# openSX70_WIP_NEW_LAYOUT_20171230_V31_man.net
KiCad netlist of a schematic drawn in EAGLE
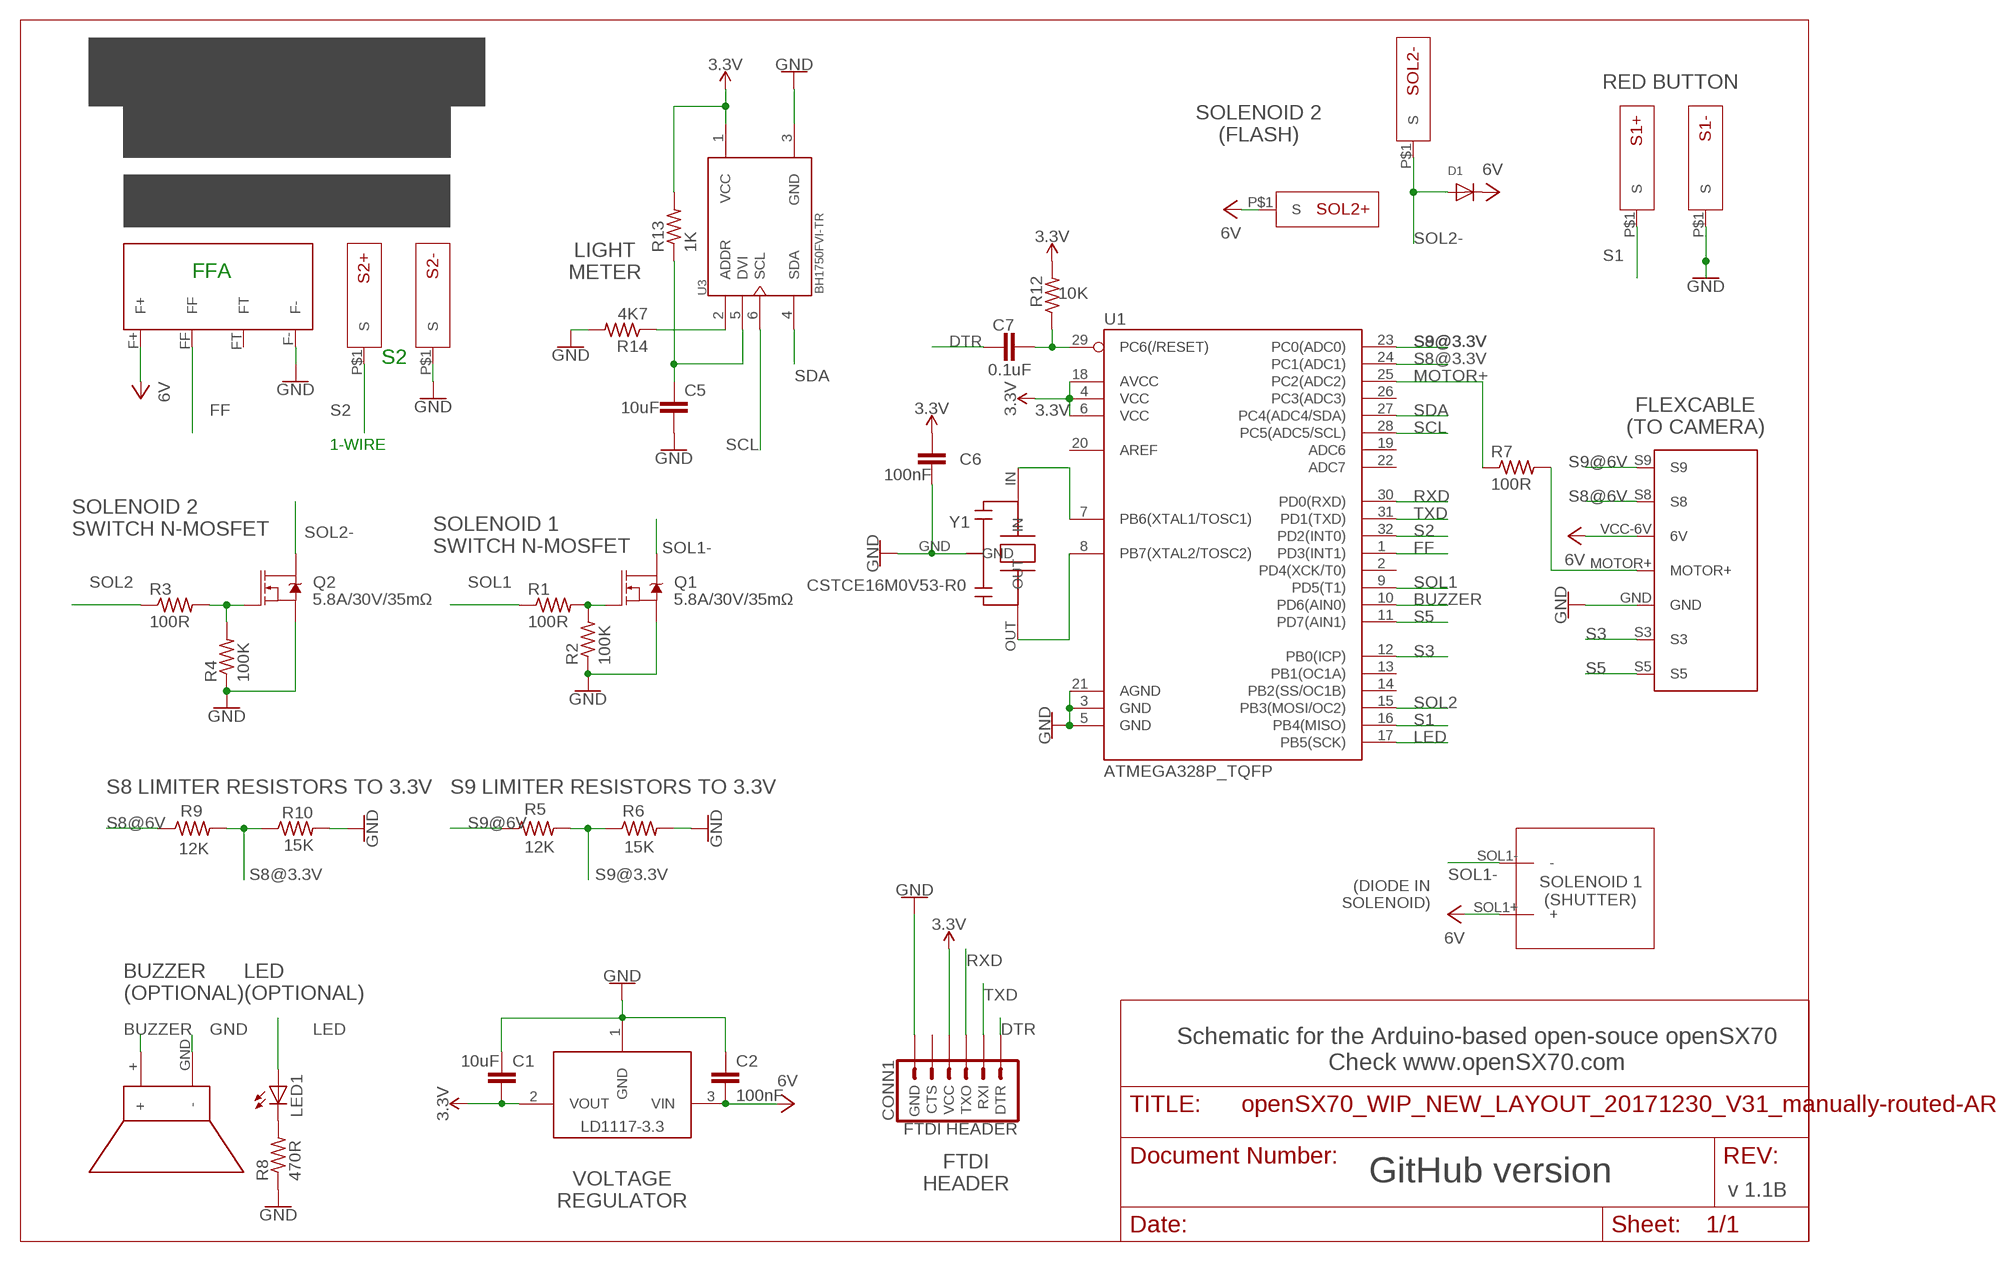
[diagram p0: schematic, sheet 1]

(export (version "E")
  (design (tool "Eeschema 10.0.6"))
  (components
    (comp (ref "BUZZ1")
      (value "CSET8-5G")
      (footprint "eagle-import:CSET8-5G_PACKAGE")
      (libsource (lib "eagle-import") (part "CSET8-5G"))
    )
    (comp (ref "C1")
      (value "10uF")
      (footprint "eagle-import:0603")
      (libsource (lib "eagle-import") (part "10UF-0603-6.3V-20%"))
    )
    (comp (ref "C2")
      (value "100nF")
      (footprint "eagle-import:C0603K")
      (libsource (lib "eagle-import") (part "C-EUC0603K"))
    )
    (comp (ref "C5")
      (value "10uF")
      (footprint "eagle-import:0603")
      (libsource (lib "eagle-import") (part "10UF-0603-6.3V-20%"))
    )
    (comp (ref "C6")
      (value "100nF")
      (footprint "eagle-import:C0805")
      (libsource (lib "eagle-import") (part "resistor_C-EUC0805"))
    )
    (comp (ref "C7")
      (value "0.1uF")
      (footprint "eagle-import:0603")
      (libsource (lib "eagle-import") (part "0.1UF-0603-25V-(+80/-20%)"))
    )
    (comp (ref "CONN1")
      (value "FTDI HEADER")
      (footprint "eagle-import:1X06")
      (libsource (lib "eagle-import") (part "6_PIN_SERIAL_TARGET"))
    )
    (comp (ref "D1")
      (value "DIODESOD-523")
      (footprint "eagle-import:SOD-523")
      (libsource (lib "eagle-import") (part "DIODESOD-523"))
    )
    (comp (ref "LD11173.3V")
      (value "LD1117 3.3V")
      (footprint "eagle-import:SOT223")
      (fields (field (name "MF") "Advanced Monolithic Systems") (field (name "MP") "AMS1117-5.0"))
      (libsource (lib "eagle-import") (part "LD1117-3.3"))
    )
    (comp (ref "LED1")
      (value "LEDCHIPLED_0805")
      (footprint "eagle-import:CHIPLED_0805")
      (libsource (lib "eagle-import") (part "LEDCHIPLED_0805"))
    )
    (comp (ref "Q1")
      (value "5.8A/30V/35mΩ")
      (footprint "eagle-import:SOT23-3")
      (libsource (lib "eagle-import") (part "MOSFET-NCH-AO3404A"))
    )
    (comp (ref "Q2")
      (value "5.8A/30V/35mΩ")
      (footprint "eagle-import:SOT23-3")
      (libsource (lib "eagle-import") (part "MOSFET-NCH-AO3404A"))
    )
    (comp (ref "R1")
      (value "100R")
      (footprint "eagle-import:R0603")
      (libsource (lib "eagle-import") (part "R-US_R0603"))
    )
    (comp (ref "R2")
      (value "100K")
      (footprint "eagle-import:R0603")
      (libsource (lib "eagle-import") (part "R-US_R0603"))
    )
    (comp (ref "R3")
      (value "100R")
      (footprint "eagle-import:R0603")
      (libsource (lib "eagle-import") (part "R-US_R0603"))
    )
    (comp (ref "R4")
      (value "100K")
      (footprint "eagle-import:R0603")
      (libsource (lib "eagle-import") (part "R-US_R0603"))
    )
    (comp (ref "R5")
      (value "12K")
      (footprint "eagle-import:R0603")
      (libsource (lib "eagle-import") (part "R-US_R0603"))
    )
    (comp (ref "R6")
      (value "15K")
      (footprint "eagle-import:R0603")
      (libsource (lib "eagle-import") (part "R-US_R0603"))
    )
    (comp (ref "R7")
      (value "100R")
      (footprint "eagle-import:R0603")
      (libsource (lib "eagle-import") (part "R-US_R0603"))
    )
    (comp (ref "R8")
      (value "470R")
      (footprint "eagle-import:R0603")
      (libsource (lib "eagle-import") (part "R-US_R0603"))
    )
    (comp (ref "R9")
      (value "12K")
      (footprint "eagle-import:R0603")
      (libsource (lib "eagle-import") (part "R-US_R0603"))
    )
    (comp (ref "R10")
      (value "15K")
      (footprint "eagle-import:R0603")
      (libsource (lib "eagle-import") (part "R-US_R0603"))
    )
    (comp (ref "R12")
      (value "10K")
      (footprint "eagle-import:R0603")
      (libsource (lib "eagle-import") (part "R-US_R0603"))
    )
    (comp (ref "R13")
      (value "1K")
      (footprint "eagle-import:R0603")
      (libsource (lib "eagle-import") (part "R-US_R0603"))
    )
    (comp (ref "R14")
      (value "4K7")
      (footprint "eagle-import:R0603")
      (libsource (lib "eagle-import") (part "R-US_R0603"))
    )
    (comp (ref "S1+")
      (value "SX70_S-PAD")
      (footprint "eagle-import:SX70-S-PAD")
      (libsource (lib "eagle-import") (part "SX70_S-PAD"))
    )
    (comp (ref "S1-")
      (value "SX70_S-PAD")
      (footprint "eagle-import:SX70-S-PAD")
      (libsource (lib "eagle-import") (part "SX70_S-PAD"))
    )
    (comp (ref "S2+")
      (value "SX70_S-PAD")
      (footprint "eagle-import:SX70-S-PAD")
      (libsource (lib "eagle-import") (part "SX70_S-PAD"))
    )
    (comp (ref "S2-")
      (value "SX70_S-PAD")
      (footprint "eagle-import:SX70-S-PAD")
      (libsource (lib "eagle-import") (part "SX70_S-PAD"))
    )
    (comp (ref "SOL1")
      (value "SX70-SOLENOID1-2PADS")
      (footprint "eagle-import:SX70-SOLENOID1-2")
      (libsource (lib "eagle-import") (part "SX70-SOLENOID1-2PADS"))
    )
    (comp (ref "SOL2+")
      (value "SX70_S-PAD")
      (footprint "eagle-import:SX70-S-PAD")
      (libsource (lib "eagle-import") (part "SX70_S-PAD"))
    )
    (comp (ref "SOL2-")
      (value "SX70_S-PAD")
      (footprint "eagle-import:SX70-S-PAD")
      (libsource (lib "eagle-import") (part "SX70_S-PAD"))
    )
    (comp (ref "U$1")
      (value "SX70-7-PAD")
      (footprint "eagle-import:SX70-7-PAD")
      (libsource (lib "eagle-import") (part "SX70-7-PAD"))
    )
    (comp (ref "U$2")
      (value "FFA")
      (footprint "eagle-import:FFA-PAD-PACKAGE")
      (libsource (lib "eagle-import") (part "SX70-FFA-PAD"))
    )
    (comp (ref "U1")
      (value "ATMEGA328P_TQFP")
      (footprint "eagle-import:TQFP32-08")
      (libsource (lib "eagle-import") (part "ATMEGA328P_TQFP"))
    )
    (comp (ref "U3")
      (value "BH1750FVI-TR")
      (footprint "eagle-import:SOTFL50P300X75-6N")
      (fields (field (name "MF") "Rohm"))
      (libsource (lib "eagle-import") (part "BH1750FVI-TR"))
    )
    (comp (ref "Y1")
      (value "CSTCE16M0V53-R0")
      (footprint "eagle-import:CFP95P160X100-3N")
      (fields (field (name "MF") "Murata"))
      (libsource (lib "eagle-import") (part "CSTCE16M0V53-R0"))
    )
  )
  (nets
    (net (code "1") (name "/BUZZER") (class "Default")
      (node (ref "BUZZ1") (pin "+") (pinfunction "+_+") (pintype "bidirectional"))
      (node (ref "U1") (pin "10") (pinfunction "PD6(AIN0)_10") (pintype "bidirectional"))
    )
    (net (code "2") (name "/DTR") (class "Default")
      (node (ref "C7") (pin "1") (pinfunction "1_1") (pintype "passive"))
      (node (ref "CONN1") (pin "1") (pinfunction "DTR_1") (pintype "passive"))
    )
    (net (code "3") (name "/FF") (class "Default")
      (node (ref "U$2") (pin "FF") (pinfunction "FF_FF") (pintype "bidirectional"))
      (node (ref "U1") (pin "1") (pinfunction "PD3(INT1)_1") (pintype "bidirectional"))
    )
    (net (code "4") (name "/LED") (class "Default")
      (node (ref "LED1") (pin "A") (pinfunction "A_A") (pintype "passive"))
      (node (ref "U1") (pin "17") (pinfunction "PB5(SCK)_17") (pintype "bidirectional"))
    )
    (net (code "5") (name "/MOTOR+") (class "Default")
      (node (ref "R7") (pin "1") (pinfunction "1_1") (pintype "passive"))
      (node (ref "U1") (pin "25") (pinfunction "PC2(ADC2)_25") (pintype "bidirectional"))
    )
    (net (code "6") (name "/RXD") (class "Default")
      (node (ref "CONN1") (pin "3") (pinfunction "TXO_3") (pintype "passive"))
      (node (ref "U1") (pin "30") (pinfunction "PD0(RXD)_30") (pintype "bidirectional"))
    )
    (net (code "7") (name "/S1") (class "Default")
      (node (ref "S1+") (pin "P$1") (pinfunction "S_P$1") (pintype "bidirectional"))
      (node (ref "U1") (pin "16") (pinfunction "PB4(MISO)_16") (pintype "bidirectional"))
    )
    (net (code "8") (name "/S2") (class "Default")
      (node (ref "S2+") (pin "P$1") (pinfunction "S_P$1") (pintype "bidirectional"))
      (node (ref "U1") (pin "32") (pinfunction "PD2(INT0)_32") (pintype "bidirectional"))
    )
    (net (code "9") (name "/S3") (class "Default")
      (node (ref "U$1") (pin "S3") (pinfunction "S3_S3") (pintype "bidirectional"))
      (node (ref "U1") (pin "12") (pinfunction "PB0(ICP)_12") (pintype "bidirectional"))
    )
    (net (code "10") (name "/S5") (class "Default")
      (node (ref "U$1") (pin "S5") (pinfunction "S5_S5") (pintype "bidirectional"))
      (node (ref "U1") (pin "11") (pinfunction "PD7(AIN1)_11") (pintype "bidirectional"))
    )
    (net (code "11") (name "/S8@3.3V") (class "Default")
      (node (ref "R10") (pin "1") (pinfunction "1_1") (pintype "passive"))
      (node (ref "R9") (pin "2") (pinfunction "2_2") (pintype "passive"))
      (node (ref "U1") (pin "24") (pinfunction "PC1(ADC1)_24") (pintype "bidirectional"))
    )
    (net (code "12") (name "/S8@6V") (class "Default")
      (node (ref "R9") (pin "1") (pinfunction "1_1") (pintype "passive"))
      (node (ref "U$1") (pin "S8") (pinfunction "S8_S8") (pintype "bidirectional"))
    )
    (net (code "13") (name "/S9@3.3V") (class "Default")
      (node (ref "R5") (pin "2") (pinfunction "2_2") (pintype "passive"))
      (node (ref "R6") (pin "1") (pinfunction "1_1") (pintype "passive"))
      (node (ref "U1") (pin "23") (pinfunction "PC0(ADC0)_23") (pintype "bidirectional"))
    )
    (net (code "14") (name "/S9@6V") (class "Default")
      (node (ref "R5") (pin "1") (pinfunction "1_1") (pintype "passive"))
      (node (ref "U$1") (pin "S9") (pinfunction "S9_S9") (pintype "bidirectional"))
    )
    (net (code "15") (name "/SCL") (class "Default")
      (node (ref "U1") (pin "28") (pinfunction "PC5(ADC5/SCL)_28") (pintype "bidirectional"))
      (node (ref "U3") (pin "6") (pinfunction "SCL_6") (pintype "input"))
    )
    (net (code "16") (name "/SDA") (class "Default")
      (node (ref "U1") (pin "27") (pinfunction "PC4(ADC4/SDA)_27") (pintype "bidirectional"))
      (node (ref "U3") (pin "4") (pinfunction "SDA_4") (pintype "bidirectional"))
    )
    (net (code "17") (name "/SOL1") (class "Default")
      (node (ref "R1") (pin "1") (pinfunction "1_1") (pintype "passive"))
      (node (ref "U1") (pin "9") (pinfunction "PD5(T1)_9") (pintype "bidirectional"))
    )
    (net (code "18") (name "/SOL1-") (class "Default")
      (node (ref "Q1") (pin "3") (pinfunction "D_3") (pintype "bidirectional"))
      (node (ref "SOL1") (pin "SOL1-") (pinfunction "-_SOL1-") (pintype "bidirectional"))
    )
    (net (code "19") (name "/SOL2") (class "Default")
      (node (ref "R3") (pin "1") (pinfunction "1_1") (pintype "passive"))
      (node (ref "U1") (pin "15") (pinfunction "PB3(MOSI/OC2)_15") (pintype "bidirectional"))
    )
    (net (code "20") (name "/SOL2-") (class "Default")
      (node (ref "D1") (pin "A") (pinfunction "A_A") (pintype "passive"))
      (node (ref "Q2") (pin "3") (pinfunction "D_3") (pintype "bidirectional"))
      (node (ref "SOL2-") (pin "P$1") (pinfunction "S_P$1") (pintype "bidirectional"))
    )
    (net (code "21") (name "/TXD") (class "Default")
      (node (ref "CONN1") (pin "2") (pinfunction "RXI_2") (pintype "passive"))
      (node (ref "U1") (pin "31") (pinfunction "PD1(TXD)_31") (pintype "bidirectional"))
    )
    (net (code "22") (name "3.3V") (class "Default")
      (node (ref "C1") (pin "2") (pinfunction "2_2") (pintype "passive"))
      (node (ref "C6") (pin "1") (pinfunction "1_1") (pintype "passive"))
      (node (ref "CONN1") (pin "4") (pinfunction "VCC_4") (pintype "passive"))
      (node (ref "LD11173.3V") (pin "2") (pinfunction "VOUT_2") (pintype "bidirectional"))
      (node (ref "R12") (pin "2") (pinfunction "2_2") (pintype "passive"))
      (node (ref "R13") (pin "2") (pinfunction "2_2") (pintype "passive"))
      (node (ref "U1") (pin "18") (pinfunction "AVCC_18") (pintype "bidirectional"))
      (node (ref "U1") (pin "4") (pinfunction "VCC_4") (pintype "bidirectional"))
      (node (ref "U1") (pin "6") (pinfunction "VCC_6") (pintype "bidirectional"))
      (node (ref "U3") (pin "1") (pinfunction "VCC_1") (pintype "power_in"))
    )
    (net (code "23") (name "6V") (class "Default")
      (node (ref "C2") (pin "2") (pinfunction "2_2") (pintype "passive"))
      (node (ref "D1") (pin "K") (pinfunction "C_K") (pintype "passive"))
      (node (ref "LD11173.3V") (pin "3") (pinfunction "VIN_3") (pintype "bidirectional"))
      (node (ref "SOL1") (pin "SOL1+") (pinfunction "+_SOL1+") (pintype "bidirectional"))
      (node (ref "SOL2+") (pin "P$1") (pinfunction "S_P$1") (pintype "bidirectional"))
      (node (ref "U$1") (pin "VCC-6V") (pinfunction "6V_VCC-6V") (pintype "bidirectional"))
      (node (ref "U$2") (pin "F+") (pinfunction "F+_F+") (pintype "bidirectional"))
    )
    (net (code "24") (name "GND") (class "Default")
      (node (ref "BUZZ1") (pin "GND") (pinfunction "-_GND") (pintype "bidirectional"))
      (node (ref "C1") (pin "1") (pinfunction "1_1") (pintype "passive"))
      (node (ref "C2") (pin "1") (pinfunction "1_1") (pintype "passive"))
      (node (ref "C5") (pin "2") (pinfunction "2_2") (pintype "passive"))
      (node (ref "C6") (pin "2") (pinfunction "2_2") (pintype "passive"))
      (node (ref "CONN1") (pin "6") (pinfunction "GND_6") (pintype "passive"))
      (node (ref "LD11173.3V") (pin "1") (pinfunction "GND_1") (pintype "bidirectional"))
      (node (ref "Q1") (pin "2") (pinfunction "S_2") (pintype "bidirectional"))
      (node (ref "Q2") (pin "2") (pinfunction "S_2") (pintype "bidirectional"))
      (node (ref "R10") (pin "2") (pinfunction "2_2") (pintype "passive"))
      (node (ref "R14") (pin "2") (pinfunction "2_2") (pintype "passive"))
      (node (ref "R2") (pin "1") (pinfunction "1_1") (pintype "passive"))
      (node (ref "R4") (pin "1") (pinfunction "1_1") (pintype "passive"))
      (node (ref "R6") (pin "2") (pinfunction "2_2") (pintype "passive"))
      (node (ref "R8") (pin "1") (pinfunction "1_1") (pintype "passive"))
      (node (ref "S1-") (pin "P$1") (pinfunction "S_P$1") (pintype "bidirectional"))
      (node (ref "S2-") (pin "P$1") (pinfunction "S_P$1") (pintype "bidirectional"))
      (node (ref "U$1") (pin "GND") (pinfunction "GND_GND") (pintype "bidirectional"))
      (node (ref "U$2") (pin "F-") (pinfunction "F-_F-") (pintype "bidirectional"))
      (node (ref "U1") (pin "21") (pinfunction "AGND_21") (pintype "bidirectional"))
      (node (ref "U1") (pin "3") (pinfunction "GND_3") (pintype "bidirectional"))
      (node (ref "U1") (pin "5") (pinfunction "GND_5") (pintype "bidirectional"))
      (node (ref "U3") (pin "3") (pinfunction "GND_3") (pintype "power_in"))
      (node (ref "Y1") (pin "GND") (pinfunction "GND_GND") (pintype "passive"))
    )
    (net (code "25") (name "Net-(LED1-PadC)") (class "Default")
      (node (ref "LED1") (pin "C") (pinfunction "C_C") (pintype "passive"))
      (node (ref "R8") (pin "2") (pinfunction "2_2") (pintype "passive"))
    )
    (net (code "26") (name "Net-(Q1-G)") (class "Default")
      (node (ref "Q1") (pin "1") (pinfunction "G_1") (pintype "bidirectional"))
      (node (ref "R1") (pin "2") (pinfunction "2_2") (pintype "passive"))
      (node (ref "R2") (pin "2") (pinfunction "2_2") (pintype "passive"))
    )
    (net (code "27") (name "Net-(Q2-G)") (class "Default")
      (node (ref "Q2") (pin "1") (pinfunction "G_1") (pintype "bidirectional"))
      (node (ref "R3") (pin "2") (pinfunction "2_2") (pintype "passive"))
      (node (ref "R4") (pin "2") (pinfunction "2_2") (pintype "passive"))
    )
    (net (code "28") (name "Net-(R7-Pad2)") (class "Default")
      (node (ref "R7") (pin "2") (pinfunction "2_2") (pintype "passive"))
      (node (ref "U$1") (pin "MOTOR+") (pinfunction "MOTOR+_MOTOR+") (pintype "bidirectional"))
    )
    (net (code "29") (name "Net-(U1-PB6(XTAL1{slash}TOSC1))") (class "Default")
      (node (ref "U1") (pin "7") (pinfunction "PB6(XTAL1/TOSC1)_7") (pintype "bidirectional"))
      (node (ref "Y1") (pin "IN") (pinfunction "IN_IN") (pintype "input"))
    )
    (net (code "30") (name "Net-(U1-PB7(XTAL2{slash}TOSC2))") (class "Default")
      (node (ref "U1") (pin "8") (pinfunction "PB7(XTAL2/TOSC2)_8") (pintype "bidirectional"))
      (node (ref "Y1") (pin "OUT") (pinfunction "OUT_OUT") (pintype "output"))
    )
    (net (code "31") (name "Net-(U1-PC6({slash}RESET))") (class "Default")
      (node (ref "C7") (pin "2") (pinfunction "2_2") (pintype "passive"))
      (node (ref "R12") (pin "1") (pinfunction "1_1") (pintype "passive"))
      (node (ref "U1") (pin "29") (pinfunction "PC6(/RESET)_29") (pintype "bidirectional"))
    )
    (net (code "32") (name "Net-(U3-ADDR)") (class "Default")
      (node (ref "R14") (pin "1") (pinfunction "1_1") (pintype "passive"))
      (node (ref "U3") (pin "2") (pinfunction "ADDR_2") (pintype "input"))
    )
    (net (code "33") (name "Net-(U3-DVI)") (class "Default")
      (node (ref "C5") (pin "1") (pinfunction "1_1") (pintype "passive"))
      (node (ref "R13") (pin "1") (pinfunction "1_1") (pintype "passive"))
      (node (ref "U3") (pin "5") (pinfunction "DVI_5") (pintype "input"))
    )
    (net (code "34") (name "unconnected-(CONN1-CTS-Pad5)") (class "Default")
      (node (ref "CONN1") (pin "5") (pinfunction "CTS_5") (pintype "passive"))
    )
    (net (code "35") (name "unconnected-(U$2-PadFT)") (class "Default")
      (node (ref "U$2") (pin "FT") (pinfunction "FT_FT") (pintype "bidirectional"))
    )
    (net (code "36") (name "unconnected-(U1-ADC6-Pad19)") (class "Default")
      (node (ref "U1") (pin "19") (pinfunction "ADC6_19") (pintype "bidirectional"))
    )
    (net (code "37") (name "unconnected-(U1-ADC7-Pad22)") (class "Default")
      (node (ref "U1") (pin "22") (pinfunction "ADC7_22") (pintype "bidirectional"))
    )
    (net (code "38") (name "unconnected-(U1-AREF-Pad20)") (class "Default")
      (node (ref "U1") (pin "20") (pinfunction "AREF_20") (pintype "bidirectional"))
    )
    (net (code "39") (name "unconnected-(U1-PB1(OC1A)-Pad13)") (class "Default")
      (node (ref "U1") (pin "13") (pinfunction "PB1(OC1A)_13") (pintype "bidirectional"))
    )
    (net (code "40") (name "unconnected-(U1-PB2(SS{slash}OC1B)-Pad14)") (class "Default")
      (node (ref "U1") (pin "14") (pinfunction "PB2(SS/OC1B)_14") (pintype "bidirectional"))
    )
    (net (code "41") (name "unconnected-(U1-PC3(ADC3)-Pad26)") (class "Default")
      (node (ref "U1") (pin "26") (pinfunction "PC3(ADC3)_26") (pintype "bidirectional"))
    )
    (net (code "42") (name "unconnected-(U1-PD4(XCK{slash}T0)-Pad2)") (class "Default")
      (node (ref "U1") (pin "2") (pinfunction "PD4(XCK/T0)_2") (pintype "bidirectional"))
    )
  )
)
